# Mk_2_2021-11-17.net
KiCad netlist of a schematic drawn in Altium Designer
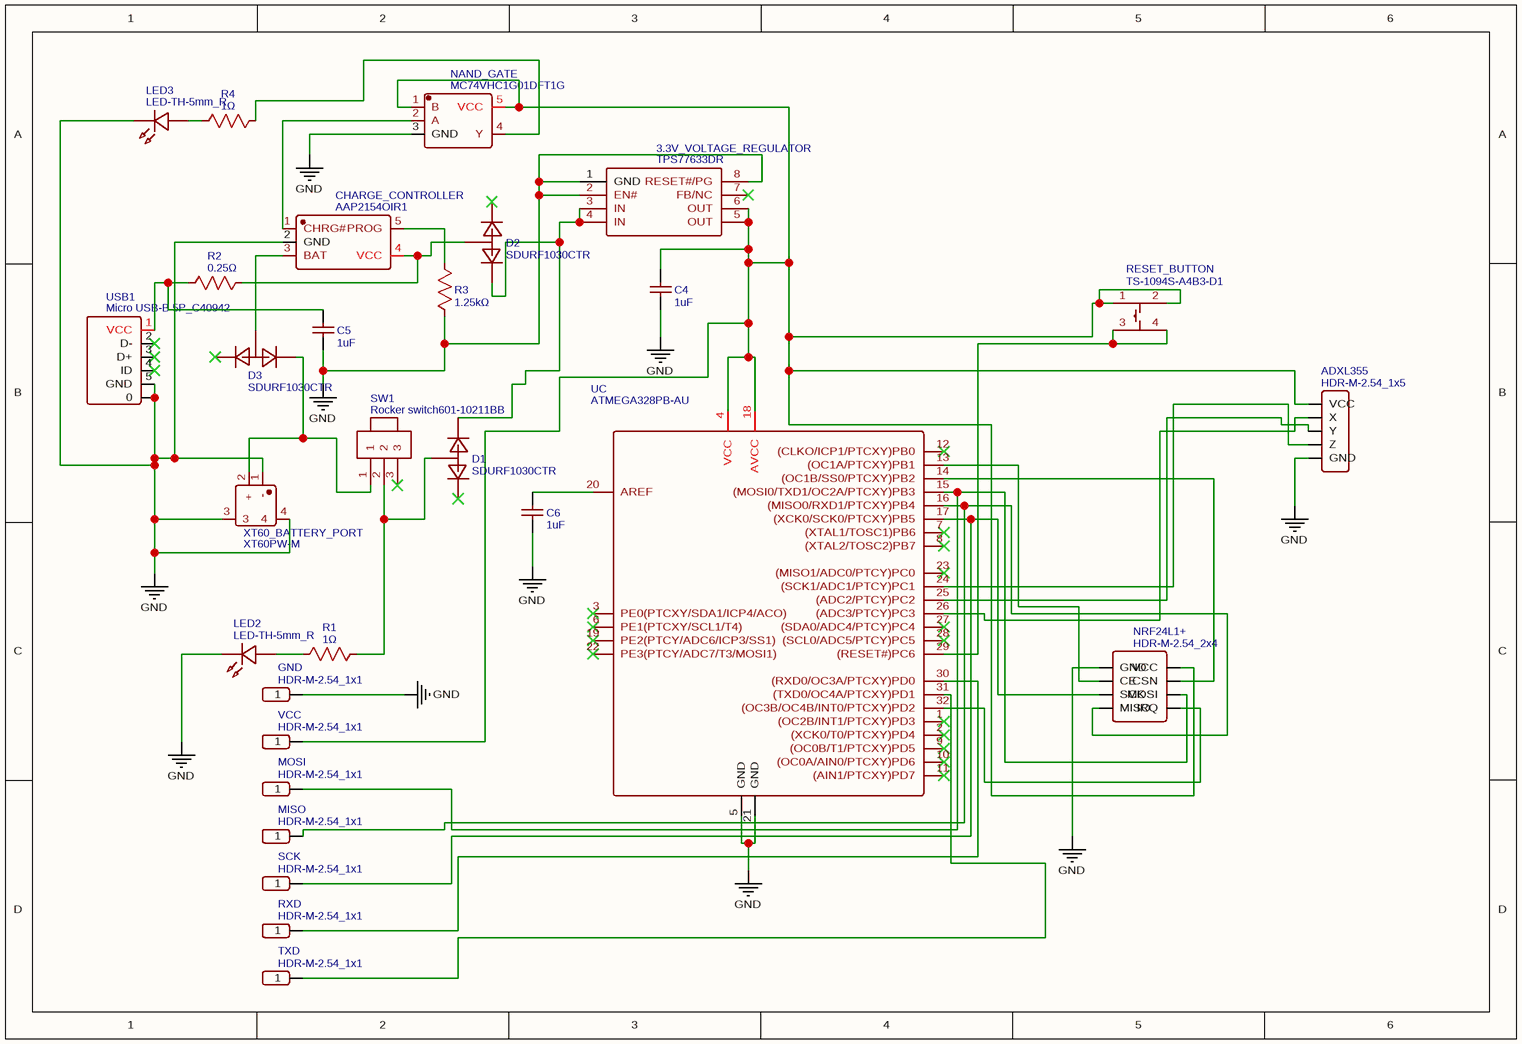
[diagram p0: Mk.2_2021-11-17.schdoc]

(export (version "E")
  (design (tool "Eeschema 10.0.6"))
  (components
    (comp (ref "3.3V_VOLTAGE_REGULATOR")
      (value "TPS77633DR")
      (fields (field (name "BOM_SUPPLIER PART") "C130078"))
      (libsource (lib "altium-import") (part "root_0_TPS77633DR_"))
    )
    (comp (ref "ADXL355")
      (value "HDR-M-2.54_1x5")
      (fields (field (name "BOM_SUPPLIER PART") "C358687") (field (name "CONTRIBUTOR") "LCEDA_Lib"))
      (libsource (lib "altium-import") (part "root_0_HDR-M-2.54_1x5_"))
    )
    (comp (ref "C4")
      (value "1uF")
      (fields
        (field (name "BOM_MANUFACTURER PART") "0603F105M250NT")
        (field (name "BOM_SUPPLIER PART") "C36577")
      )
      (libsource (lib "altium-import") (part "root_3_1uF_"))
    )
    (comp (ref "C5")
      (value "1uF")
      (fields
        (field (name "BOM_MANUFACTURER PART") "0603F105M250NT")
        (field (name "BOM_SUPPLIER PART") "C36577")
      )
      (libsource (lib "altium-import") (part "root_3_1uF_"))
    )
    (comp (ref "C6")
      (value "1uF")
      (fields
        (field (name "BOM_MANUFACTURER PART") "0603F105M250NT")
        (field (name "BOM_SUPPLIER PART") "C36577")
      )
      (libsource (lib "altium-import") (part "root_3_1uF_"))
    )
    (comp (ref "CHARGE_CONTROLLER")
      (value "AAP2154OIR1")
      (fields (field (name "BOM_SUPPLIER PART") "C370749") (field (name "CONTRIBUTOR") "LCSC"))
      (libsource (lib "altium-import") (part "root_0_AAP2154OIR1_"))
    )
    (comp (ref "D1")
      (value "SDURF1030CTR")
      (fields (field (name "BOM_SUPPLIER PART") "C260371") (field (name "CONTRIBUTOR") "LCSC"))
      (libsource (lib "altium-import") (part "root_3_SDURF1030CTR_"))
    )
    (comp (ref "D2")
      (value "SDURF1030CTR")
      (fields (field (name "BOM_SUPPLIER PART") "C260371") (field (name "CONTRIBUTOR") "LCSC"))
      (libsource (lib "altium-import") (part "root_3_SDURF1030CTR_"))
    )
    (comp (ref "D3")
      (value "SDURF1030CTR")
      (fields (field (name "BOM_SUPPLIER PART") "C260371") (field (name "CONTRIBUTOR") "LCSC"))
      (libsource (lib "altium-import") (part "root_2_SDURF1030CTR_"))
    )
    (comp (ref "GND")
      (value "HDR-M-2.54_1x1")
      (fields (field (name "BOM_SUPPLIER PART") "C81276") (field (name "CONTRIBUTOR") "LCEDA_Lib"))
      (libsource (lib "altium-import") (part "root_2_HDR-M-2.54_1x1_"))
    )
    (comp (ref "LED2")
      (value "LED-TH-5mm_R")
      (fields
        (field (name "BOM_MANUFACTURER PART") "333-2SURD/S530-A3")
        (field (name "BOM_SUPPLIER PART") "C87271")
        (field (name "CONTRIBUTOR") "LCEDA_Lib")
      )
      (libsource (lib "altium-import") (part "root_2_LED-TH-5mm_R_"))
    )
    (comp (ref "LED3")
      (value "LED-TH-5mm_R")
      (fields
        (field (name "BOM_MANUFACTURER PART") "333-2SURD/S530-A3")
        (field (name "BOM_SUPPLIER PART") "C87271")
        (field (name "CONTRIBUTOR") "LCEDA_Lib")
      )
      (libsource (lib "altium-import") (part "root_2_LED-TH-5mm_R_"))
    )
    (comp (ref "MISO")
      (value "HDR-M-2.54_1x1")
      (fields (field (name "BOM_SUPPLIER PART") "C81276") (field (name "CONTRIBUTOR") "LCEDA_Lib"))
      (libsource (lib "altium-import") (part "root_2_HDR-M-2.54_1x1_"))
    )
    (comp (ref "MOSI")
      (value "HDR-M-2.54_1x1")
      (fields (field (name "BOM_SUPPLIER PART") "C81276") (field (name "CONTRIBUTOR") "LCEDA_Lib"))
      (libsource (lib "altium-import") (part "root_2_HDR-M-2.54_1x1_"))
    )
    (comp (ref "NAND_GATE")
      (value "MC74VHC1G01DFT1G")
      (fields (field (name "BOM_SUPPLIER PART") "C150244") (field (name "CONTRIBUTOR") "LCSC"))
      (libsource (lib "altium-import") (part "root_0_MC74VHC1G01DFT1G_"))
    )
    (comp (ref "NRF24L1+")
      (value "HDR-M-2.54_2x4")
      (fields (field (name "BOM_SUPPLIER PART") "C58363") (field (name "CONTRIBUTOR") "LCEDA_Lib"))
      (libsource (lib "altium-import") (part "root_0_HDR-M-2.54_2x4_"))
    )
    (comp (ref "R1")
      (value "1Ω")
      (fields (field (name "CONTRIBUTOR") "LCEDA_Lib"))
      (libsource (lib "altium-import") (part "root_0_1Ω_"))
    )
    (comp (ref "R2")
      (value "0.25Ω")
      (fields (field (name "CONTRIBUTOR") "LCEDA_Lib"))
      (libsource (lib "altium-import") (part "root_0_0.25Ω_"))
    )
    (comp (ref "R3")
      (value "1.25kΩ")
      (fields (field (name "CONTRIBUTOR") "LCEDA_Lib"))
      (libsource (lib "altium-import") (part "root_1_1.25kΩ_"))
    )
    (comp (ref "R4")
      (value "1Ω")
      (fields (field (name "CONTRIBUTOR") "LCEDA_Lib"))
      (libsource (lib "altium-import") (part "root_0_1Ω_"))
    )
    (comp (ref "RESET_BUTTON")
      (value "TS-1094S-A4B3-D1")
      (fields (field (name "BOM_SUPPLIER PART") "C492972") (field (name "CONTRIBUTOR") "LCSC"))
      (libsource (lib "altium-import") (part "root_0_TS-1094S-A4B3-D1_"))
    )
    (comp (ref "RXD")
      (value "HDR-M-2.54_1x1")
      (fields (field (name "BOM_SUPPLIER PART") "C81276") (field (name "CONTRIBUTOR") "LCEDA_Lib"))
      (libsource (lib "altium-import") (part "root_2_HDR-M-2.54_1x1_"))
    )
    (comp (ref "SCK")
      (value "HDR-M-2.54_1x1")
      (fields (field (name "BOM_SUPPLIER PART") "C81276") (field (name "CONTRIBUTOR") "LCEDA_Lib"))
      (libsource (lib "altium-import") (part "root_2_HDR-M-2.54_1x1_"))
    )
    (comp (ref "SW1")
      (value "Rocker switch601-10211BB")
      (fields (field (name "BOM_SUPPLIER PART") "C67849"))
      (libsource (lib "altium-import") (part "root_0_Rocker switch601-10211BB_"))
    )
    (comp (ref "TXD")
      (value "HDR-M-2.54_1x1")
      (fields (field (name "BOM_SUPPLIER PART") "C81276") (field (name "CONTRIBUTOR") "LCEDA_Lib"))
      (libsource (lib "altium-import") (part "root_2_HDR-M-2.54_1x1_"))
    )
    (comp (ref "UC")
      (value "ATMEGA328PB-AU")
      (fields (field (name "BOM_SUPPLIER PART") "C132230") (field (name "CONTRIBUTOR") "LCSC"))
      (libsource (lib "altium-import") (part "root_0_ATMEGA328PB-AU_"))
    )
    (comp (ref "USB1")
      (value "Micro USB-B 5P_C40942")
      (fields (field (name "BOM_SUPPLIER PART") "C40942"))
      (libsource (lib "altium-import") (part "root_0_Micro USB-B 5P_C40942_"))
    )
    (comp (ref "VCC")
      (value "HDR-M-2.54_1x1")
      (fields (field (name "BOM_SUPPLIER PART") "C81276") (field (name "CONTRIBUTOR") "LCEDA_Lib"))
      (libsource (lib "altium-import") (part "root_2_HDR-M-2.54_1x1_"))
    )
    (comp (ref "XT60_BATTERY_PORT")
      (value "XT60PW-M")
      (fields (field (name "BOM_SUPPLIER PART") "C98732") (field (name "CONTRIBUTOR") "LCSC"))
      (libsource (lib "altium-import") (part "root_3_XT60PW-M_"))
    )
  )
  (nets
    (net (code "1") (name "GND") (class "Default")
      (node (ref "3.3V_VOLTAGE_REGULATOR") (pin "1") (pinfunction "GND_1") (pintype "passive"))
      (node (ref "3.3V_VOLTAGE_REGULATOR") (pin "2") (pinfunction "EN#_2") (pintype "passive"))
      (node (ref "3.3V_VOLTAGE_REGULATOR") (pin "8") (pinfunction "RESET#/PG_8") (pintype "passive"))
      (node (ref "ADXL355") (pin "5") (pinfunction "GND_5") (pintype "passive"))
      (node (ref "C4") (pin "2") (pinfunction "2_2") (pintype "passive"))
      (node (ref "C5") (pin "2") (pinfunction "2_2") (pintype "passive"))
      (node (ref "C6") (pin "2") (pinfunction "2_2") (pintype "passive"))
      (node (ref "CHARGE_CONTROLLER") (pin "2") (pinfunction "GND_2") (pintype "passive"))
      (node (ref "GND") (pin "1") (pinfunction "1_1") (pintype "passive"))
      (node (ref "LED2") (pin "2") (pinfunction "2_2") (pintype "passive"))
      (node (ref "LED3") (pin "2") (pinfunction "2_2") (pintype "passive"))
      (node (ref "NAND_GATE") (pin "3") (pinfunction "GND_3") (pintype "passive"))
      (node (ref "NRF24L1+") (pin "1") (pinfunction "GND_1") (pintype "passive"))
      (node (ref "R3") (pin "1") (pinfunction "1_1") (pintype "passive"))
      (node (ref "UC") (pin "21") (pinfunction "GND_21") (pintype "passive"))
      (node (ref "UC") (pin "5") (pinfunction "GND_5") (pintype "passive"))
      (node (ref "USB1") (pin "0") (pinfunction "0_0") (pintype "passive"))
      (node (ref "USB1") (pin "5") (pinfunction "GND_5") (pintype "passive"))
      (node (ref "XT60_BATTERY_PORT") (pin "1") (pinfunction "-_1") (pintype "passive"))
      (node (ref "XT60_BATTERY_PORT") (pin "3") (pinfunction "3_3") (pintype "passive"))
      (node (ref "XT60_BATTERY_PORT") (pin "4") (pinfunction "4_4") (pintype "passive"))
    )
    (net (code "2") (name "Net-(3.3V_VOLTAGE_REGULATOR-IN-Pad3)") (class "Default")
      (node (ref "3.3V_VOLTAGE_REGULATOR") (pin "3") (pinfunction "IN_3") (pintype "passive"))
      (node (ref "3.3V_VOLTAGE_REGULATOR") (pin "4") (pinfunction "IN_4") (pintype "passive"))
      (node (ref "D1") (pin "1") (pinfunction "C_1") (pintype "passive"))
      (node (ref "D2") (pin "3") (pinfunction "C_3") (pintype "passive"))
    )
    (net (code "3") (name "Net-(ADXL355-VCC)") (class "Default")
      (node (ref "3.3V_VOLTAGE_REGULATOR") (pin "5") (pinfunction "OUT_5") (pintype "passive"))
      (node (ref "3.3V_VOLTAGE_REGULATOR") (pin "6") (pinfunction "OUT_6") (pintype "passive"))
      (node (ref "ADXL355") (pin "1") (pinfunction "VCC_1") (pintype "passive"))
      (node (ref "C4") (pin "1") (pinfunction "1_1") (pintype "passive"))
      (node (ref "NAND_GATE") (pin "1") (pinfunction "B_1") (pintype "passive"))
      (node (ref "NAND_GATE") (pin "5") (pinfunction "VCC_5") (pintype "passive"))
      (node (ref "NRF24L1+") (pin "2") (pinfunction "VCC_2") (pintype "passive"))
      (node (ref "RESET_BUTTON") (pin "1") (pinfunction "1_1") (pintype "passive"))
      (node (ref "RESET_BUTTON") (pin "2") (pinfunction "2_2") (pintype "passive"))
      (node (ref "UC") (pin "18") (pinfunction "AVCC_18") (pintype "passive"))
      (node (ref "UC") (pin "4") (pinfunction "VCC_4") (pintype "passive"))
      (node (ref "VCC") (pin "1") (pinfunction "1_1") (pintype "passive"))
    )
    (net (code "4") (name "Net-(ADXL355-X)") (class "Default")
      (node (ref "ADXL355") (pin "2") (pinfunction "X_2") (pintype "passive"))
      (node (ref "UC") (pin "26") (pinfunction "(ADC3/PTCY)PC3_26") (pintype "passive"))
    )
    (net (code "5") (name "Net-(ADXL355-Y)") (class "Default")
      (node (ref "ADXL355") (pin "3") (pinfunction "Y_3") (pintype "passive"))
      (node (ref "UC") (pin "25") (pinfunction "(ADC2/PTCY)PC2_25") (pintype "passive"))
    )
    (net (code "6") (name "Net-(ADXL355-Z)") (class "Default")
      (node (ref "ADXL355") (pin "4") (pinfunction "Z_4") (pintype "passive"))
      (node (ref "UC") (pin "24") (pinfunction "(SCK1/ADC1/PTCY)PC1_24") (pintype "passive"))
    )
    (net (code "7") (name "Net-(CHARGE_CONTROLLER-BAT)") (class "Default")
      (node (ref "CHARGE_CONTROLLER") (pin "3") (pinfunction "BAT_3") (pintype "passive"))
      (node (ref "D3") (pin "2") (pinfunction "A_2") (pintype "passive"))
    )
    (net (code "8") (name "Net-(CHARGE_CONTROLLER-CHRG#)") (class "Default")
      (node (ref "CHARGE_CONTROLLER") (pin "1") (pinfunction "CHRG#_1") (pintype "passive"))
      (node (ref "NAND_GATE") (pin "2") (pinfunction "A_2") (pintype "passive"))
    )
    (net (code "9") (name "Net-(CHARGE_CONTROLLER-PROG)") (class "Default")
      (node (ref "CHARGE_CONTROLLER") (pin "5") (pinfunction "PROG_5") (pintype "passive"))
      (node (ref "R3") (pin "2") (pinfunction "2_2") (pintype "passive"))
    )
    (net (code "10") (name "Net-(CHARGE_CONTROLLER-VCC)") (class "Default")
      (node (ref "CHARGE_CONTROLLER") (pin "4") (pinfunction "VCC_4") (pintype "passive"))
      (node (ref "D2") (pin "2") (pinfunction "A_2") (pintype "passive"))
      (node (ref "R2") (pin "2") (pinfunction "2_2") (pintype "passive"))
    )
    (net (code "11") (name "Net-(D1-A)") (class "Default")
      (node (ref "D1") (pin "2") (pinfunction "A_2") (pintype "passive"))
      (node (ref "R1") (pin "2") (pinfunction "2_2") (pintype "passive"))
      (node (ref "SW1") (pin "2") (pinfunction "2_2") (pintype "passive"))
    )
    (net (code "12") (name "Net-(LED2-Pad1)") (class "Default")
      (node (ref "LED2") (pin "1") (pinfunction "1_1") (pintype "passive"))
      (node (ref "R1") (pin "1") (pinfunction "1_1") (pintype "passive"))
    )
    (net (code "13") (name "Net-(LED3-Pad1)") (class "Default")
      (node (ref "LED3") (pin "1") (pinfunction "1_1") (pintype "passive"))
      (node (ref "R4") (pin "1") (pinfunction "1_1") (pintype "passive"))
    )
    (net (code "14") (name "Net-(NAND_GATE-Y)") (class "Default")
      (node (ref "NAND_GATE") (pin "4") (pinfunction "Y_4") (pintype "passive"))
      (node (ref "R4") (pin "2") (pinfunction "2_2") (pintype "passive"))
    )
    (net (code "15") (name "Net-(NRF24L1+-CE)") (class "Default")
      (node (ref "NRF24L1+") (pin "3") (pinfunction "CE_3") (pintype "passive"))
      (node (ref "UC") (pin "13") (pinfunction "(OC1A/PTCXY)PB1_13") (pintype "passive"))
    )
    (net (code "16") (name "Net-(NRF24L1+-CSN)") (class "Default")
      (node (ref "NRF24L1+") (pin "4") (pinfunction "CSN_4") (pintype "passive"))
      (node (ref "UC") (pin "14") (pinfunction "(OC1B/SS0/PTCXY)PB2_14") (pintype "passive"))
    )
    (net (code "17") (name "Net-(NRF24L1+-IRQ)") (class "Default")
      (node (ref "NRF24L1+") (pin "8") (pinfunction "IRQ_8") (pintype "passive"))
      (node (ref "UC") (pin "32") (pinfunction "(OC3B/OC4B/INT0/PTCXY)PD2_32") (pintype "passive"))
    )
    (net (code "18") (name "Net-(NRF24L1+-MISO)") (class "Default")
      (node (ref "MISO") (pin "1") (pinfunction "1_1") (pintype "passive"))
      (node (ref "NRF24L1+") (pin "7") (pinfunction "MISO_7") (pintype "passive"))
      (node (ref "UC") (pin "16") (pinfunction "(MISO0/RXD1/PTCXY)PB4_16") (pintype "passive"))
    )
    (net (code "19") (name "Net-(NRF24L1+-MOSI)") (class "Default")
      (node (ref "MOSI") (pin "1") (pinfunction "1_1") (pintype "passive"))
      (node (ref "NRF24L1+") (pin "6") (pinfunction "MOSI_6") (pintype "passive"))
      (node (ref "UC") (pin "15") (pinfunction "(MOSI0/TXD1/OC2A/PTCXY)PB3_15") (pintype "passive"))
    )
    (net (code "20") (name "Net-(NRF24L1+-SCK)") (class "Default")
      (node (ref "NRF24L1+") (pin "5") (pinfunction "SCK_5") (pintype "passive"))
      (node (ref "SCK") (pin "1") (pinfunction "1_1") (pintype "passive"))
      (node (ref "UC") (pin "17") (pinfunction "(XCK0/SCK0/PTCXY)PB5_17") (pintype "passive"))
    )
    (net (code "21") (name "Net-(UC-(RESET#)PC6)") (class "Default")
      (node (ref "RESET_BUTTON") (pin "3") (pinfunction "3_3") (pintype "passive"))
      (node (ref "RESET_BUTTON") (pin "4") (pinfunction "4_4") (pintype "passive"))
      (node (ref "UC") (pin "29") (pinfunction "(RESET#)PC6_29") (pintype "passive"))
    )
    (net (code "22") (name "Net-(UC-(RXD0{slash}OC3A{slash}PTCXY)PD0)") (class "Default")
      (node (ref "RXD") (pin "1") (pinfunction "1_1") (pintype "passive"))
      (node (ref "UC") (pin "30") (pinfunction "(RXD0/OC3A/PTCXY)PD0_30") (pintype "passive"))
    )
    (net (code "23") (name "Net-(UC-(TXD0{slash}OC4A{slash}PTCXY)PD1)") (class "Default")
      (node (ref "TXD") (pin "1") (pinfunction "1_1") (pintype "passive"))
      (node (ref "UC") (pin "31") (pinfunction "(TXD0/OC4A/PTCXY)PD1_31") (pintype "passive"))
    )
    (net (code "24") (name "Net-(UC-AREF)") (class "Default")
      (node (ref "C6") (pin "1") (pinfunction "1_1") (pintype "passive"))
      (node (ref "UC") (pin "20") (pinfunction "AREF_20") (pintype "passive"))
    )
    (net (code "25") (name "Net-(USB1-VCC)") (class "Default")
      (node (ref "C5") (pin "1") (pinfunction "1_1") (pintype "passive"))
      (node (ref "R2") (pin "1") (pinfunction "1_1") (pintype "passive"))
      (node (ref "USB1") (pin "1") (pinfunction "VCC_1") (pintype "passive"))
    )
    (net (code "26") (name "Net-(XT60_BATTERY_PORT-+)") (class "Default")
      (node (ref "D3") (pin "1") (pinfunction "C_1") (pintype "passive"))
      (node (ref "SW1") (pin "1") (pinfunction "1_1") (pintype "passive"))
      (node (ref "XT60_BATTERY_PORT") (pin "2") (pinfunction "+_2") (pintype "passive"))
    )
    (net (code "27") (name "unconnected-(3.3V_VOLTAGE_REGULATOR-FB{slash}NC-Pad7)") (class "Default")
      (node (ref "3.3V_VOLTAGE_REGULATOR") (pin "7") (pinfunction "FB/NC_7") (pintype "passive+no_connect"))
    )
    (net (code "28") (name "unconnected-(D1-C-Pad3)") (class "Default")
      (node (ref "D1") (pin "3") (pinfunction "C_3") (pintype "passive+no_connect"))
    )
    (net (code "29") (name "unconnected-(D2-C-Pad1)") (class "Default")
      (node (ref "D2") (pin "1") (pinfunction "C_1") (pintype "passive+no_connect"))
    )
    (net (code "30") (name "unconnected-(D3-C-Pad3)") (class "Default")
      (node (ref "D3") (pin "3") (pinfunction "C_3") (pintype "passive+no_connect"))
    )
    (net (code "31") (name "unconnected-(SW1-Pad3)") (class "Default")
      (node (ref "SW1") (pin "3") (pinfunction "3_3") (pintype "passive+no_connect"))
    )
    (net (code "32") (name "unconnected-(UC-(AIN1{slash}PTCXY)PD7-Pad11)") (class "Default")
      (node (ref "UC") (pin "11") (pinfunction "(AIN1/PTCXY)PD7_11") (pintype "passive+no_connect"))
    )
    (net (code "33") (name "unconnected-(UC-(CLKO{slash}ICP1{slash}PTCXY)PB0-Pad12)") (class "Default")
      (node (ref "UC") (pin "12") (pinfunction "(CLKO/ICP1/PTCXY)PB0_12") (pintype "passive+no_connect"))
    )
    (net (code "34") (name "unconnected-(UC-(MISO1{slash}ADC0{slash}PTCY)PC0-Pad23)") (class "Default")
      (node (ref "UC") (pin "23") (pinfunction "(MISO1/ADC0/PTCY)PC0_23") (pintype "passive+no_connect"))
    )
    (net (code "35") (name "unconnected-(UC-(OC0A{slash}AIN0{slash}PTCXY)PD6-Pad10)") (class "Default")
      (node (ref "UC") (pin "10") (pinfunction "(OC0A/AIN0/PTCXY)PD6_10") (pintype "passive+no_connect"))
    )
    (net (code "36") (name "unconnected-(UC-(OC0B{slash}T1{slash}PTCXY)PD5-Pad9)") (class "Default")
      (node (ref "UC") (pin "9") (pinfunction "(OC0B/T1/PTCXY)PD5_9") (pintype "passive+no_connect"))
    )
    (net (code "37") (name "unconnected-(UC-(OC2B{slash}INT1{slash}PTCXY)PD3-Pad1)") (class "Default")
      (node (ref "UC") (pin "1") (pinfunction "(OC2B/INT1/PTCXY)PD3_1") (pintype "passive+no_connect"))
    )
    (net (code "38") (name "unconnected-(UC-(SCL0{slash}ADC5{slash}PTCY)PC5-Pad28)") (class "Default")
      (node (ref "UC") (pin "28") (pinfunction "(SCL0/ADC5/PTCY)PC5_28") (pintype "passive+no_connect"))
    )
    (net (code "39") (name "unconnected-(UC-(SDA0{slash}ADC4{slash}PTCY)PC4-Pad27)") (class "Default")
      (node (ref "UC") (pin "27") (pinfunction "(SDA0/ADC4/PTCY)PC4_27") (pintype "passive+no_connect"))
    )
    (net (code "40") (name "unconnected-(UC-(XCK0{slash}T0{slash}PTCXY)PD4-Pad2)") (class "Default")
      (node (ref "UC") (pin "2") (pinfunction "(XCK0/T0/PTCXY)PD4_2") (pintype "passive+no_connect"))
    )
    (net (code "41") (name "unconnected-(UC-(XTAL1{slash}TOSC1)PB6-Pad7)") (class "Default")
      (node (ref "UC") (pin "7") (pinfunction "(XTAL1/TOSC1)PB6_7") (pintype "passive+no_connect"))
    )
    (net (code "42") (name "unconnected-(UC-(XTAL2{slash}TOSC2)PB7-Pad8)") (class "Default")
      (node (ref "UC") (pin "8") (pinfunction "(XTAL2/TOSC2)PB7_8") (pintype "passive+no_connect"))
    )
    (net (code "43") (name "unconnected-(UC-PE0(PTCXY{slash}SDA1{slash}ICP4{slash}ACO)-Pad3)") (class "Default")
      (node (ref "UC") (pin "3") (pinfunction "PE0(PTCXY/SDA1/ICP4/ACO)_3") (pintype "passive+no_connect"))
    )
    (net (code "44") (name "unconnected-(UC-PE1(PTCXY{slash}SCL1{slash}T4)-Pad6)") (class "Default")
      (node (ref "UC") (pin "6") (pinfunction "PE1(PTCXY/SCL1/T4)_6") (pintype "passive+no_connect"))
    )
    (net (code "45") (name "unconnected-(UC-PE2(PTCY{slash}ADC6{slash}ICP3{slash}SS1)-Pad19)") (class "Default")
      (node (ref "UC") (pin "19") (pinfunction "PE2(PTCY/ADC6/ICP3/SS1)_19") (pintype "passive+no_connect"))
    )
    (net (code "46") (name "unconnected-(UC-PE3(PTCY{slash}ADC7{slash}T3{slash}MOSI1)-Pad22)") (class "Default")
      (node (ref "UC") (pin "22") (pinfunction "PE3(PTCY/ADC7/T3/MOSI1)_22") (pintype "passive+no_connect"))
    )
    (net (code "47") (name "unconnected-(USB1-D+-Pad3)") (class "Default")
      (node (ref "USB1") (pin "3") (pinfunction "D+_3") (pintype "passive+no_connect"))
    )
    (net (code "48") (name "unconnected-(USB1-D--Pad2)") (class "Default")
      (node (ref "USB1") (pin "2") (pinfunction "D-_2") (pintype "passive+no_connect"))
    )
    (net (code "49") (name "unconnected-(USB1-ID-Pad4)") (class "Default")
      (node (ref "USB1") (pin "4") (pinfunction "ID_4") (pintype "passive+no_connect"))
    )
  )
)
